# mixtape2.net
KiCad netlist of a schematic drawn in EAGLE
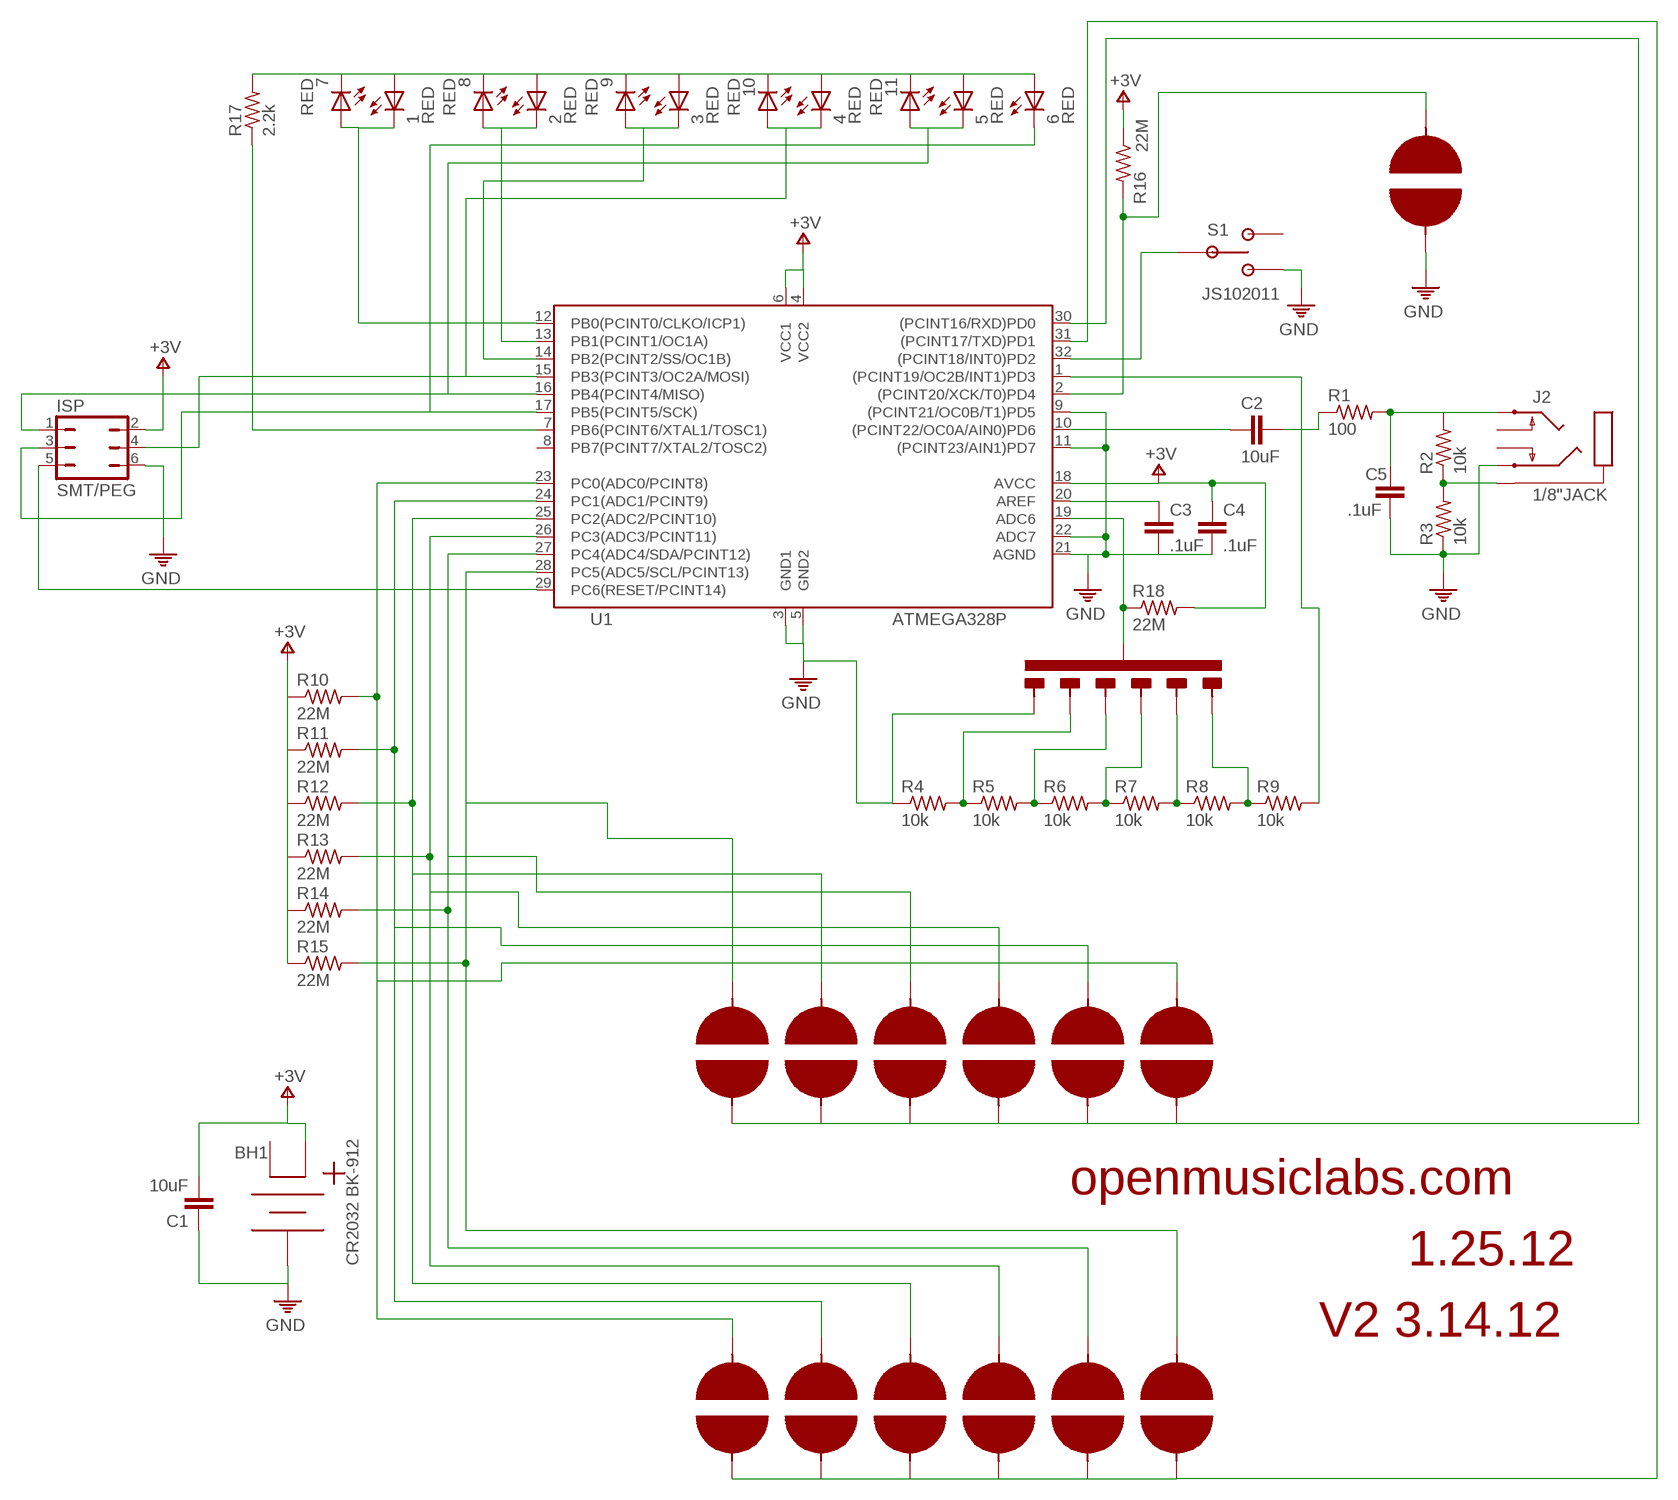
[diagram p0: schematic, sheet 1]

(export (version "E")
  (design (tool "Eeschema 10.0.6"))
  (components
    (comp (ref "1")
      (value "RED")
      (footprint "eagle-import:LED-SMT-91-21")
      (libsource (lib "eagle-import") (part "LEDLUMEX-92-21"))
    )
    (comp (ref "2")
      (value "RED")
      (footprint "eagle-import:LED-SMT-91-21")
      (libsource (lib "eagle-import") (part "LEDLUMEX-92-21"))
    )
    (comp (ref "3")
      (value "RED")
      (footprint "eagle-import:LED-SMT-91-21")
      (libsource (lib "eagle-import") (part "LEDLUMEX-92-21"))
    )
    (comp (ref "4")
      (value "RED")
      (footprint "eagle-import:LED-SMT-91-21")
      (libsource (lib "eagle-import") (part "LEDLUMEX-92-21"))
    )
    (comp (ref "5")
      (value "RED")
      (footprint "eagle-import:LED-SMT-91-21")
      (libsource (lib "eagle-import") (part "LEDLUMEX-92-21"))
    )
    (comp (ref "6")
      (value "RED")
      (footprint "eagle-import:LED-SMT-91-21")
      (libsource (lib "eagle-import") (part "LEDLUMEX-92-21"))
    )
    (comp (ref "7")
      (value "RED")
      (footprint "eagle-import:LED-SMT-91-21")
      (libsource (lib "eagle-import") (part "LEDLUMEX-92-21"))
    )
    (comp (ref "8")
      (value "RED")
      (footprint "eagle-import:LED-SMT-91-21")
      (libsource (lib "eagle-import") (part "LEDLUMEX-92-21"))
    )
    (comp (ref "9")
      (value "RED")
      (footprint "eagle-import:LED-SMT-91-21")
      (libsource (lib "eagle-import") (part "LEDLUMEX-92-21"))
    )
    (comp (ref "10")
      (value "RED")
      (footprint "eagle-import:LED-SMT-91-21")
      (libsource (lib "eagle-import") (part "LEDLUMEX-92-21"))
    )
    (comp (ref "11")
      (value "RED")
      (footprint "eagle-import:LED-SMT-91-21")
      (libsource (lib "eagle-import") (part "LEDLUMEX-92-21"))
    )
    (comp (ref "BH1")
      (value "CR2032 BK-912")
      (footprint "eagle-import:BAT-HOLD-BK-912")
      (libsource (lib "eagle-import") (part "BAT-HOLDCR2032-BK-912"))
    )
    (comp (ref "C1")
      (value "10uF")
      (footprint "eagle-import:0805_SMALL")
      (libsource (lib "eagle-import") (part "CAPACITOR0805-SM"))
    )
    (comp (ref "C2")
      (value "10uF")
      (footprint "eagle-import:0805_SMALL")
      (libsource (lib "eagle-import") (part "CAPACITOR0805-SM"))
    )
    (comp (ref "C3")
      (value ".1uF")
      (footprint "eagle-import:0603-SM")
      (libsource (lib "eagle-import") (part "CAPACITOR0603=SM"))
    )
    (comp (ref "C4")
      (value ".1uF")
      (footprint "eagle-import:0603-SM")
      (libsource (lib "eagle-import") (part "CAPACITOR0603=SM"))
    )
    (comp (ref "C5")
      (value ".1uF")
      (footprint "eagle-import:0603-SM")
      (libsource (lib "eagle-import") (part "CAPACITOR0603=SM"))
    )
    (comp (ref "ISP")
      (value "SMT/PEG")
      (footprint "eagle-import:JMP_6P_DIP_SMT_PEG")
      (libsource (lib "eagle-import") (part "JMP/6P/DIPSMT/PEG"))
    )
    (comp (ref "J2")
      (value "1/8\"JACK")
      (footprint "eagle-import:1_8_JACK_STEREO_SMT")
      (libsource (lib "eagle-import") (part "1/8{dblquote}JACK/STEREO/2SWITCHCUI3515/KOBICONN2805"))
    )
    (comp (ref "R1")
      (value "100")
      (footprint "eagle-import:0603-SM")
      (libsource (lib "eagle-import") (part "RESISTOR0603-SM"))
    )
    (comp (ref "R2")
      (value "10k")
      (footprint "eagle-import:0603-SM")
      (libsource (lib "eagle-import") (part "RESISTOR0603-SM"))
    )
    (comp (ref "R3")
      (value "10k")
      (footprint "eagle-import:0603-SM")
      (libsource (lib "eagle-import") (part "RESISTOR0603-SM"))
    )
    (comp (ref "R4")
      (value "10k")
      (footprint "eagle-import:0603-SM")
      (libsource (lib "eagle-import") (part "RESISTOR0603-SM"))
    )
    (comp (ref "R5")
      (value "10k")
      (footprint "eagle-import:0603-SM")
      (libsource (lib "eagle-import") (part "RESISTOR0603-SM"))
    )
    (comp (ref "R6")
      (value "10k")
      (footprint "eagle-import:0603-SM")
      (libsource (lib "eagle-import") (part "RESISTOR0603-SM"))
    )
    (comp (ref "R7")
      (value "10k")
      (footprint "eagle-import:0603-SM")
      (libsource (lib "eagle-import") (part "RESISTOR0603-SM"))
    )
    (comp (ref "R8")
      (value "10k")
      (footprint "eagle-import:0603-SM")
      (libsource (lib "eagle-import") (part "RESISTOR0603-SM"))
    )
    (comp (ref "R9")
      (value "10k")
      (footprint "eagle-import:0603-SM")
      (libsource (lib "eagle-import") (part "RESISTOR0603-SM"))
    )
    (comp (ref "R10")
      (value "22M")
      (footprint "eagle-import:0603-SM")
      (libsource (lib "eagle-import") (part "RESISTOR0603-SM"))
    )
    (comp (ref "R11")
      (value "22M")
      (footprint "eagle-import:0603-SM")
      (libsource (lib "eagle-import") (part "RESISTOR0603-SM"))
    )
    (comp (ref "R12")
      (value "22M")
      (footprint "eagle-import:0603-SM")
      (libsource (lib "eagle-import") (part "RESISTOR0603-SM"))
    )
    (comp (ref "R13")
      (value "22M")
      (footprint "eagle-import:0603-SM")
      (libsource (lib "eagle-import") (part "RESISTOR0603-SM"))
    )
    (comp (ref "R14")
      (value "22M")
      (footprint "eagle-import:0603-SM")
      (libsource (lib "eagle-import") (part "RESISTOR0603-SM"))
    )
    (comp (ref "R15")
      (value "22M")
      (footprint "eagle-import:0603-SM")
      (libsource (lib "eagle-import") (part "RESISTOR0603-SM"))
    )
    (comp (ref "R16")
      (value "22M")
      (footprint "eagle-import:0603-SM")
      (libsource (lib "eagle-import") (part "RESISTOR0603-SM"))
    )
    (comp (ref "R17")
      (value "2.2k")
      (footprint "eagle-import:0603-SM")
      (libsource (lib "eagle-import") (part "RESISTOR0603-SM"))
    )
    (comp (ref "R18")
      (value "22M")
      (footprint "eagle-import:0603-SM")
      (libsource (lib "eagle-import") (part "RESISTOR0603-SM"))
    )
    (comp (ref "S1")
      (value "JS102011")
      (footprint "eagle-import:SWITCH_SLIDE_JS102011")
      (libsource (lib "eagle-import") (part "SWITCH/SPDT/NOMECHJS102011"))
    )
    (comp (ref "U$1")
      (value "PAD/TOUCH/WHEEL")
      (footprint "eagle-import:PAD_TOUCH_WHEEL")
      (libsource (lib "eagle-import") (part "PAD/TOUCH/WHEEL"))
    )
    (comp (ref "U$2")
      (value "PAD/TOUCH")
      (footprint "eagle-import:PAD_TOUCH_DOT")
      (libsource (lib "eagle-import") (part "PAD/TOUCH"))
    )
    (comp (ref "U$3")
      (value "PAD/TOUCH")
      (footprint "eagle-import:PAD_TOUCH_DOT")
      (libsource (lib "eagle-import") (part "PAD/TOUCH"))
    )
    (comp (ref "U$4")
      (value "PAD/TOUCH")
      (footprint "eagle-import:PAD_TOUCH_DOT")
      (libsource (lib "eagle-import") (part "PAD/TOUCH"))
    )
    (comp (ref "U$5")
      (value "PAD/TOUCH")
      (footprint "eagle-import:PAD_TOUCH_DOT")
      (libsource (lib "eagle-import") (part "PAD/TOUCH"))
    )
    (comp (ref "U$6")
      (value "PAD/TOUCH")
      (footprint "eagle-import:PAD_TOUCH_DOT")
      (libsource (lib "eagle-import") (part "PAD/TOUCH"))
    )
    (comp (ref "U$7")
      (value "PAD/TOUCH")
      (footprint "eagle-import:PAD_TOUCH_DOT")
      (libsource (lib "eagle-import") (part "PAD/TOUCH"))
    )
    (comp (ref "U$8")
      (value "PAD/TOUCH")
      (footprint "eagle-import:PAD_TOUCH_DOT")
      (libsource (lib "eagle-import") (part "PAD/TOUCH"))
    )
    (comp (ref "U$9")
      (value "PAD/TOUCH/SLIDERSLIDER")
      (footprint "eagle-import:PAD_TOUCH_SLIDER")
      (libsource (lib "eagle-import") (part "PAD/TOUCH/SLIDERSLIDER"))
    )
    (comp (ref "U1")
      (value "ATMEGA328P")
      (footprint "eagle-import:32-TQFP-NOMOD")
      (libsource (lib "eagle-import") (part "ATMEGA328P"))
    )
  )
  (nets
    (net (code "1") (name "+3V") (class "Default")
      (node (ref "BH1") (pin "P$1") (pinfunction "P$3_P$1") (pintype "bidirectional"))
      (node (ref "C1") (pin "2") (pinfunction "2_2") (pintype "passive"))
      (node (ref "C4") (pin "P$1") (pinfunction "1_P$1") (pintype "passive"))
      (node (ref "ISP") (pin "2") (pinfunction "2_2") (pintype "passive"))
      (node (ref "R10") (pin "P$1") (pinfunction "1_P$1") (pintype "passive"))
      (node (ref "R11") (pin "P$1") (pinfunction "1_P$1") (pintype "passive"))
      (node (ref "R12") (pin "P$1") (pinfunction "1_P$1") (pintype "passive"))
      (node (ref "R13") (pin "P$1") (pinfunction "1_P$1") (pintype "passive"))
      (node (ref "R14") (pin "P$1") (pinfunction "1_P$1") (pintype "passive"))
      (node (ref "R15") (pin "P$1") (pinfunction "1_P$1") (pintype "passive"))
      (node (ref "R16") (pin "P$1") (pinfunction "1_P$1") (pintype "passive"))
      (node (ref "R18") (pin "P$2") (pinfunction "2_P$2") (pintype "passive"))
      (node (ref "U1") (pin "18") (pinfunction "AVCC_18") (pintype "bidirectional"))
      (node (ref "U1") (pin "4") (pinfunction "VCC2_4") (pintype "bidirectional"))
      (node (ref "U1") (pin "6") (pinfunction "VCC1_6") (pintype "bidirectional"))
    )
    (net (code "2") (name "GND") (class "Default")
      (node (ref "BH1") (pin "P$3") (pinfunction "P$1_P$3") (pintype "bidirectional"))
      (node (ref "C1") (pin "1") (pinfunction "1_1") (pintype "passive"))
      (node (ref "C3") (pin "P$2") (pinfunction "2_P$2") (pintype "passive"))
      (node (ref "C4") (pin "P$2") (pinfunction "2_P$2") (pintype "passive"))
      (node (ref "C5") (pin "P$2") (pinfunction "2_P$2") (pintype "passive"))
      (node (ref "ISP") (pin "6") (pinfunction "6_6") (pintype "passive"))
      (node (ref "J2") (pin "P$3") (pinfunction "2_P$3") (pintype "passive"))
      (node (ref "R3") (pin "P$1") (pinfunction "1_P$1") (pintype "passive"))
      (node (ref "R4") (pin "P$1") (pinfunction "1_P$1") (pintype "passive"))
      (node (ref "S1") (pin "P$1") (pinfunction "P$3_P$1") (pintype "bidirectional"))
      (node (ref "U$8") (pin "P$2") (pinfunction "P$2_P$2") (pintype "bidirectional"))
      (node (ref "U$9") (pin "P$7") (pinfunction "P$7_P$7") (pintype "bidirectional"))
      (node (ref "U1") (pin "11") (pinfunction "(PCINT23/AIN1)PD7_11") (pintype "bidirectional"))
      (node (ref "U1") (pin "21") (pinfunction "AGND_21") (pintype "bidirectional"))
      (node (ref "U1") (pin "22") (pinfunction "ADC7_22") (pintype "bidirectional"))
      (node (ref "U1") (pin "3") (pinfunction "GND1_3") (pintype "bidirectional"))
      (node (ref "U1") (pin "5") (pinfunction "GND2_5") (pintype "bidirectional"))
      (node (ref "U1") (pin "9") (pinfunction "(PCINT21/OC0B/T1)PD5_9") (pintype "bidirectional"))
    )
    (net (code "3") (name "Net-(1-A)") (class "Default")
      (node (ref "1") (pin "P$2") (pinfunction "A_P$2") (pintype "passive"))
      (node (ref "10") (pin "P$1") (pinfunction "C_P$1") (pintype "passive"))
      (node (ref "11") (pin "P$1") (pinfunction "C_P$1") (pintype "passive"))
      (node (ref "2") (pin "P$2") (pinfunction "A_P$2") (pintype "passive"))
      (node (ref "3") (pin "P$2") (pinfunction "A_P$2") (pintype "passive"))
      (node (ref "4") (pin "P$2") (pinfunction "A_P$2") (pintype "passive"))
      (node (ref "5") (pin "P$2") (pinfunction "A_P$2") (pintype "passive"))
      (node (ref "6") (pin "P$2") (pinfunction "A_P$2") (pintype "passive"))
      (node (ref "7") (pin "P$1") (pinfunction "C_P$1") (pintype "passive"))
      (node (ref "8") (pin "P$1") (pinfunction "C_P$1") (pintype "passive"))
      (node (ref "9") (pin "P$1") (pinfunction "C_P$1") (pintype "passive"))
      (node (ref "R17") (pin "P$2") (pinfunction "2_P$2") (pintype "passive"))
    )
    (net (code "4") (name "Net-(1-C)") (class "Default")
      (node (ref "1") (pin "P$1") (pinfunction "C_P$1") (pintype "passive"))
      (node (ref "7") (pin "P$2") (pinfunction "A_P$2") (pintype "passive"))
      (node (ref "U1") (pin "12") (pinfunction "PB0(PCINT0/CLKO/ICP1)_12") (pintype "bidirectional"))
    )
    (net (code "5") (name "Net-(2-C)") (class "Default")
      (node (ref "2") (pin "P$1") (pinfunction "C_P$1") (pintype "passive"))
      (node (ref "8") (pin "P$2") (pinfunction "A_P$2") (pintype "passive"))
      (node (ref "U1") (pin "13") (pinfunction "PB1(PCINT1/OC1A)_13") (pintype "bidirectional"))
    )
    (net (code "6") (name "Net-(3-C)") (class "Default")
      (node (ref "3") (pin "P$1") (pinfunction "C_P$1") (pintype "passive"))
      (node (ref "9") (pin "P$2") (pinfunction "A_P$2") (pintype "passive"))
      (node (ref "U1") (pin "14") (pinfunction "PB2(PCINT2/SS/OC1B)_14") (pintype "bidirectional"))
    )
    (net (code "7") (name "Net-(6-C)") (class "Default")
      (node (ref "6") (pin "P$1") (pinfunction "C_P$1") (pintype "passive"))
      (node (ref "ISP") (pin "3") (pinfunction "3_3") (pintype "passive"))
      (node (ref "U1") (pin "17") (pinfunction "PB5(PCINT5/SCK)_17") (pintype "bidirectional"))
    )
    (net (code "8") (name "Net-(10-A)") (class "Default")
      (node (ref "10") (pin "P$2") (pinfunction "A_P$2") (pintype "passive"))
      (node (ref "4") (pin "P$1") (pinfunction "C_P$1") (pintype "passive"))
      (node (ref "ISP") (pin "4") (pinfunction "4_4") (pintype "passive"))
      (node (ref "U1") (pin "15") (pinfunction "PB3(PCINT3/OC2A/MOSI)_15") (pintype "bidirectional"))
    )
    (net (code "9") (name "Net-(11-A)") (class "Default")
      (node (ref "11") (pin "P$2") (pinfunction "A_P$2") (pintype "passive"))
      (node (ref "5") (pin "P$1") (pinfunction "C_P$1") (pintype "passive"))
      (node (ref "ISP") (pin "1") (pinfunction "1_1") (pintype "passive"))
      (node (ref "U1") (pin "16") (pinfunction "PB4(PCINT4/MISO)_16") (pintype "bidirectional"))
    )
    (net (code "10") (name "Net-(C3-1)") (class "Default")
      (node (ref "C3") (pin "P$1") (pinfunction "1_P$1") (pintype "passive"))
      (node (ref "U1") (pin "20") (pinfunction "AREF_20") (pintype "bidirectional"))
    )
    (net (code "11") (name "Net-(C5-1)") (class "Default")
      (node (ref "C5") (pin "P$1") (pinfunction "1_P$1") (pintype "passive"))
      (node (ref "J2") (pin "P$5") (pinfunction "5_P$5") (pintype "passive"))
      (node (ref "R1") (pin "P$2") (pinfunction "2_P$2") (pintype "passive"))
      (node (ref "R2") (pin "P$2") (pinfunction "2_P$2") (pintype "passive"))
    )
    (net (code "12") (name "Net-(J2-1)") (class "Default")
      (node (ref "J2") (pin "P$1") (pinfunction "1_P$1") (pintype "passive"))
      (node (ref "R2") (pin "P$1") (pinfunction "1_P$1") (pintype "passive"))
      (node (ref "R3") (pin "P$2") (pinfunction "2_P$2") (pintype "passive"))
    )
    (net (code "13") (name "Net-(R1-1)") (class "Default")
      (node (ref "C2") (pin "1") (pinfunction "1_1") (pintype "passive"))
      (node (ref "R1") (pin "P$1") (pinfunction "1_P$1") (pintype "passive"))
    )
    (net (code "14") (name "Net-(R4-2)") (class "Default")
      (node (ref "R4") (pin "P$2") (pinfunction "2_P$2") (pintype "passive"))
      (node (ref "R5") (pin "P$1") (pinfunction "1_P$1") (pintype "passive"))
      (node (ref "U$9") (pin "P$6") (pinfunction "P$6_P$6") (pintype "bidirectional"))
    )
    (net (code "15") (name "Net-(R5-2)") (class "Default")
      (node (ref "R5") (pin "P$2") (pinfunction "2_P$2") (pintype "passive"))
      (node (ref "R6") (pin "P$1") (pinfunction "1_P$1") (pintype "passive"))
      (node (ref "U$9") (pin "P$5") (pinfunction "P$5_P$5") (pintype "bidirectional"))
    )
    (net (code "16") (name "Net-(R6-2)") (class "Default")
      (node (ref "R6") (pin "P$2") (pinfunction "2_P$2") (pintype "passive"))
      (node (ref "R7") (pin "P$1") (pinfunction "1_P$1") (pintype "passive"))
      (node (ref "U$9") (pin "P$4") (pinfunction "P$4_P$4") (pintype "bidirectional"))
    )
    (net (code "17") (name "Net-(R7-2)") (class "Default")
      (node (ref "R7") (pin "P$2") (pinfunction "2_P$2") (pintype "passive"))
      (node (ref "R8") (pin "P$1") (pinfunction "1_P$1") (pintype "passive"))
      (node (ref "U$9") (pin "P$3") (pinfunction "P$3_P$3") (pintype "bidirectional"))
    )
    (net (code "18") (name "Net-(R8-2)") (class "Default")
      (node (ref "R8") (pin "P$2") (pinfunction "2_P$2") (pintype "passive"))
      (node (ref "R9") (pin "P$1") (pinfunction "1_P$1") (pintype "passive"))
      (node (ref "U$9") (pin "P$2") (pinfunction "P$2_P$2") (pintype "bidirectional"))
    )
    (net (code "19") (name "Net-(R9-2)") (class "Default")
      (node (ref "R9") (pin "P$2") (pinfunction "2_P$2") (pintype "passive"))
      (node (ref "U1") (pin "1") (pinfunction "(PCINT19/OC2B/INT1)PD3_1") (pintype "bidirectional"))
    )
    (net (code "20") (name "Net-(R10-2)") (class "Default")
      (node (ref "R10") (pin "P$2") (pinfunction "2_P$2") (pintype "passive"))
      (node (ref "U$1") (pin "P$11") (pinfunction "P$1_P$11") (pintype "bidirectional"))
      (node (ref "U$2") (pin "P$1") (pinfunction "P$1_P$1") (pintype "bidirectional"))
      (node (ref "U1") (pin "23") (pinfunction "PC0(ADC0/PCINT8)_23") (pintype "bidirectional"))
    )
    (net (code "21") (name "Net-(R11-2)") (class "Default")
      (node (ref "R11") (pin "P$2") (pinfunction "2_P$2") (pintype "passive"))
      (node (ref "U$1") (pin "P$9") (pinfunction "P$1_P$9") (pintype "bidirectional"))
      (node (ref "U$3") (pin "P$1") (pinfunction "P$1_P$1") (pintype "bidirectional"))
      (node (ref "U1") (pin "24") (pinfunction "PC1(ADC1/PCINT9)_24") (pintype "bidirectional"))
    )
    (net (code "22") (name "Net-(R12-2)") (class "Default")
      (node (ref "R12") (pin "P$2") (pinfunction "2_P$2") (pintype "passive"))
      (node (ref "U$1") (pin "P$3") (pinfunction "P$1_P$3") (pintype "bidirectional"))
      (node (ref "U$4") (pin "P$1") (pinfunction "P$1_P$1") (pintype "bidirectional"))
      (node (ref "U1") (pin "25") (pinfunction "PC2(ADC2/PCINT10)_25") (pintype "bidirectional"))
    )
    (net (code "23") (name "Net-(R13-2)") (class "Default")
      (node (ref "R13") (pin "P$2") (pinfunction "2_P$2") (pintype "passive"))
      (node (ref "U$1") (pin "P$7") (pinfunction "P$1_P$7") (pintype "bidirectional"))
      (node (ref "U$5") (pin "P$1") (pinfunction "P$1_P$1") (pintype "bidirectional"))
      (node (ref "U1") (pin "26") (pinfunction "PC3(ADC3/PCINT11)_26") (pintype "bidirectional"))
    )
    (net (code "24") (name "Net-(R14-2)") (class "Default")
      (node (ref "R14") (pin "P$2") (pinfunction "2_P$2") (pintype "passive"))
      (node (ref "U$1") (pin "P$5") (pinfunction "P$1_P$5") (pintype "bidirectional"))
      (node (ref "U$6") (pin "P$1") (pinfunction "P$1_P$1") (pintype "bidirectional"))
      (node (ref "U1") (pin "27") (pinfunction "PC4(ADC4/SDA/PCINT12)_27") (pintype "bidirectional"))
    )
    (net (code "25") (name "Net-(R15-2)") (class "Default")
      (node (ref "R15") (pin "P$2") (pinfunction "2_P$2") (pintype "passive"))
      (node (ref "U$1") (pin "P$1") (pinfunction "P$1_P$1") (pintype "bidirectional"))
      (node (ref "U$7") (pin "P$1") (pinfunction "P$1_P$1") (pintype "bidirectional"))
      (node (ref "U1") (pin "28") (pinfunction "PC5(ADC5/SCL/PCINT13)_28") (pintype "bidirectional"))
    )
    (net (code "26") (name "Net-(R16-2)") (class "Default")
      (node (ref "R16") (pin "P$2") (pinfunction "2_P$2") (pintype "passive"))
      (node (ref "U$8") (pin "P$1") (pinfunction "P$1_P$1") (pintype "bidirectional"))
      (node (ref "U1") (pin "2") (pinfunction "(PCINT20/XCK/T0)PD4_2") (pintype "bidirectional"))
    )
    (net (code "27") (name "Net-(R17-1)") (class "Default")
      (node (ref "R17") (pin "P$1") (pinfunction "1_P$1") (pintype "passive"))
      (node (ref "U1") (pin "7") (pinfunction "PB6(PCINT6/XTAL1/TOSC1)_7") (pintype "bidirectional"))
    )
    (net (code "28") (name "Net-(R18-1)") (class "Default")
      (node (ref "R18") (pin "P$1") (pinfunction "1_P$1") (pintype "passive"))
      (node (ref "U$9") (pin "P$1") (pinfunction "P$1_P$1") (pintype "bidirectional"))
      (node (ref "U1") (pin "19") (pinfunction "ADC6_19") (pintype "bidirectional"))
    )
    (net (code "29") (name "Net-(S1-P$1)") (class "Default")
      (node (ref "S1") (pin "P$2") (pinfunction "P$1_P$2") (pintype "bidirectional"))
      (node (ref "U1") (pin "32") (pinfunction "(PCINT18/INT0)PD2_32") (pintype "bidirectional"))
    )
    (net (code "30") (name "Net-(U$1B-P$2)") (class "Default")
      (node (ref "U$1") (pin "P$10") (pinfunction "P$2_P$10") (pintype "bidirectional"))
      (node (ref "U$1") (pin "P$12") (pinfunction "P$2_P$12") (pintype "bidirectional"))
      (node (ref "U$1") (pin "P$2") (pinfunction "P$2_P$2") (pintype "bidirectional"))
      (node (ref "U$1") (pin "P$4") (pinfunction "P$2_P$4") (pintype "bidirectional"))
      (node (ref "U$1") (pin "P$6") (pinfunction "P$2_P$6") (pintype "bidirectional"))
      (node (ref "U$1") (pin "P$8") (pinfunction "P$2_P$8") (pintype "bidirectional"))
      (node (ref "U1") (pin "30") (pinfunction "(PCINT16/RXD)PD0_30") (pintype "bidirectional"))
    )
    (net (code "31") (name "Net-(U1-(PCINT17{slash}TXD)PD1)") (class "Default")
      (node (ref "U$2") (pin "P$2") (pinfunction "P$2_P$2") (pintype "bidirectional"))
      (node (ref "U$3") (pin "P$2") (pinfunction "P$2_P$2") (pintype "bidirectional"))
      (node (ref "U$4") (pin "P$2") (pinfunction "P$2_P$2") (pintype "bidirectional"))
      (node (ref "U$5") (pin "P$2") (pinfunction "P$2_P$2") (pintype "bidirectional"))
      (node (ref "U$6") (pin "P$2") (pinfunction "P$2_P$2") (pintype "bidirectional"))
      (node (ref "U$7") (pin "P$2") (pinfunction "P$2_P$2") (pintype "bidirectional"))
      (node (ref "U1") (pin "31") (pinfunction "(PCINT17/TXD)PD1_31") (pintype "bidirectional"))
    )
    (net (code "32") (name "Net-(U1-(PCINT22{slash}OC0A{slash}AIN0)PD6)") (class "Default")
      (node (ref "C2") (pin "2") (pinfunction "2_2") (pintype "passive"))
      (node (ref "U1") (pin "10") (pinfunction "(PCINT22/OC0A/AIN0)PD6_10") (pintype "bidirectional"))
    )
    (net (code "33") (name "Net-(U1-PC6(RESET{slash}PCINT14))") (class "Default")
      (node (ref "ISP") (pin "5") (pinfunction "5_5") (pintype "passive"))
      (node (ref "U1") (pin "29") (pinfunction "PC6(RESET/PCINT14)_29") (pintype "bidirectional"))
    )
    (net (code "34") (name "unconnected-(BH1-PadP$2)") (class "Default")
      (node (ref "BH1") (pin "P$2") (pinfunction "P$2_P$2") (pintype "bidirectional"))
    )
    (net (code "35") (name "unconnected-(J2-3-PadP$2)") (class "Default")
      (node (ref "J2") (pin "P$2") (pinfunction "3_P$2") (pintype "passive"))
    )
    (net (code "36") (name "unconnected-(J2-4-PadP$4)") (class "Default")
      (node (ref "J2") (pin "P$4") (pinfunction "4_P$4") (pintype "passive"))
    )
    (net (code "37") (name "unconnected-(S1-P$2-PadP$3)") (class "Default")
      (node (ref "S1") (pin "P$3") (pinfunction "P$2_P$3") (pintype "bidirectional"))
    )
    (net (code "38") (name "unconnected-(U1-PB7(PCINT7{slash}XTAL2{slash}TOSC2)-Pad8)") (class "Default")
      (node (ref "U1") (pin "8") (pinfunction "PB7(PCINT7/XTAL2/TOSC2)_8") (pintype "bidirectional"))
    )
  )
)
